# v0_4_0.net
KiCad netlist of a schematic drawn in EAGLE
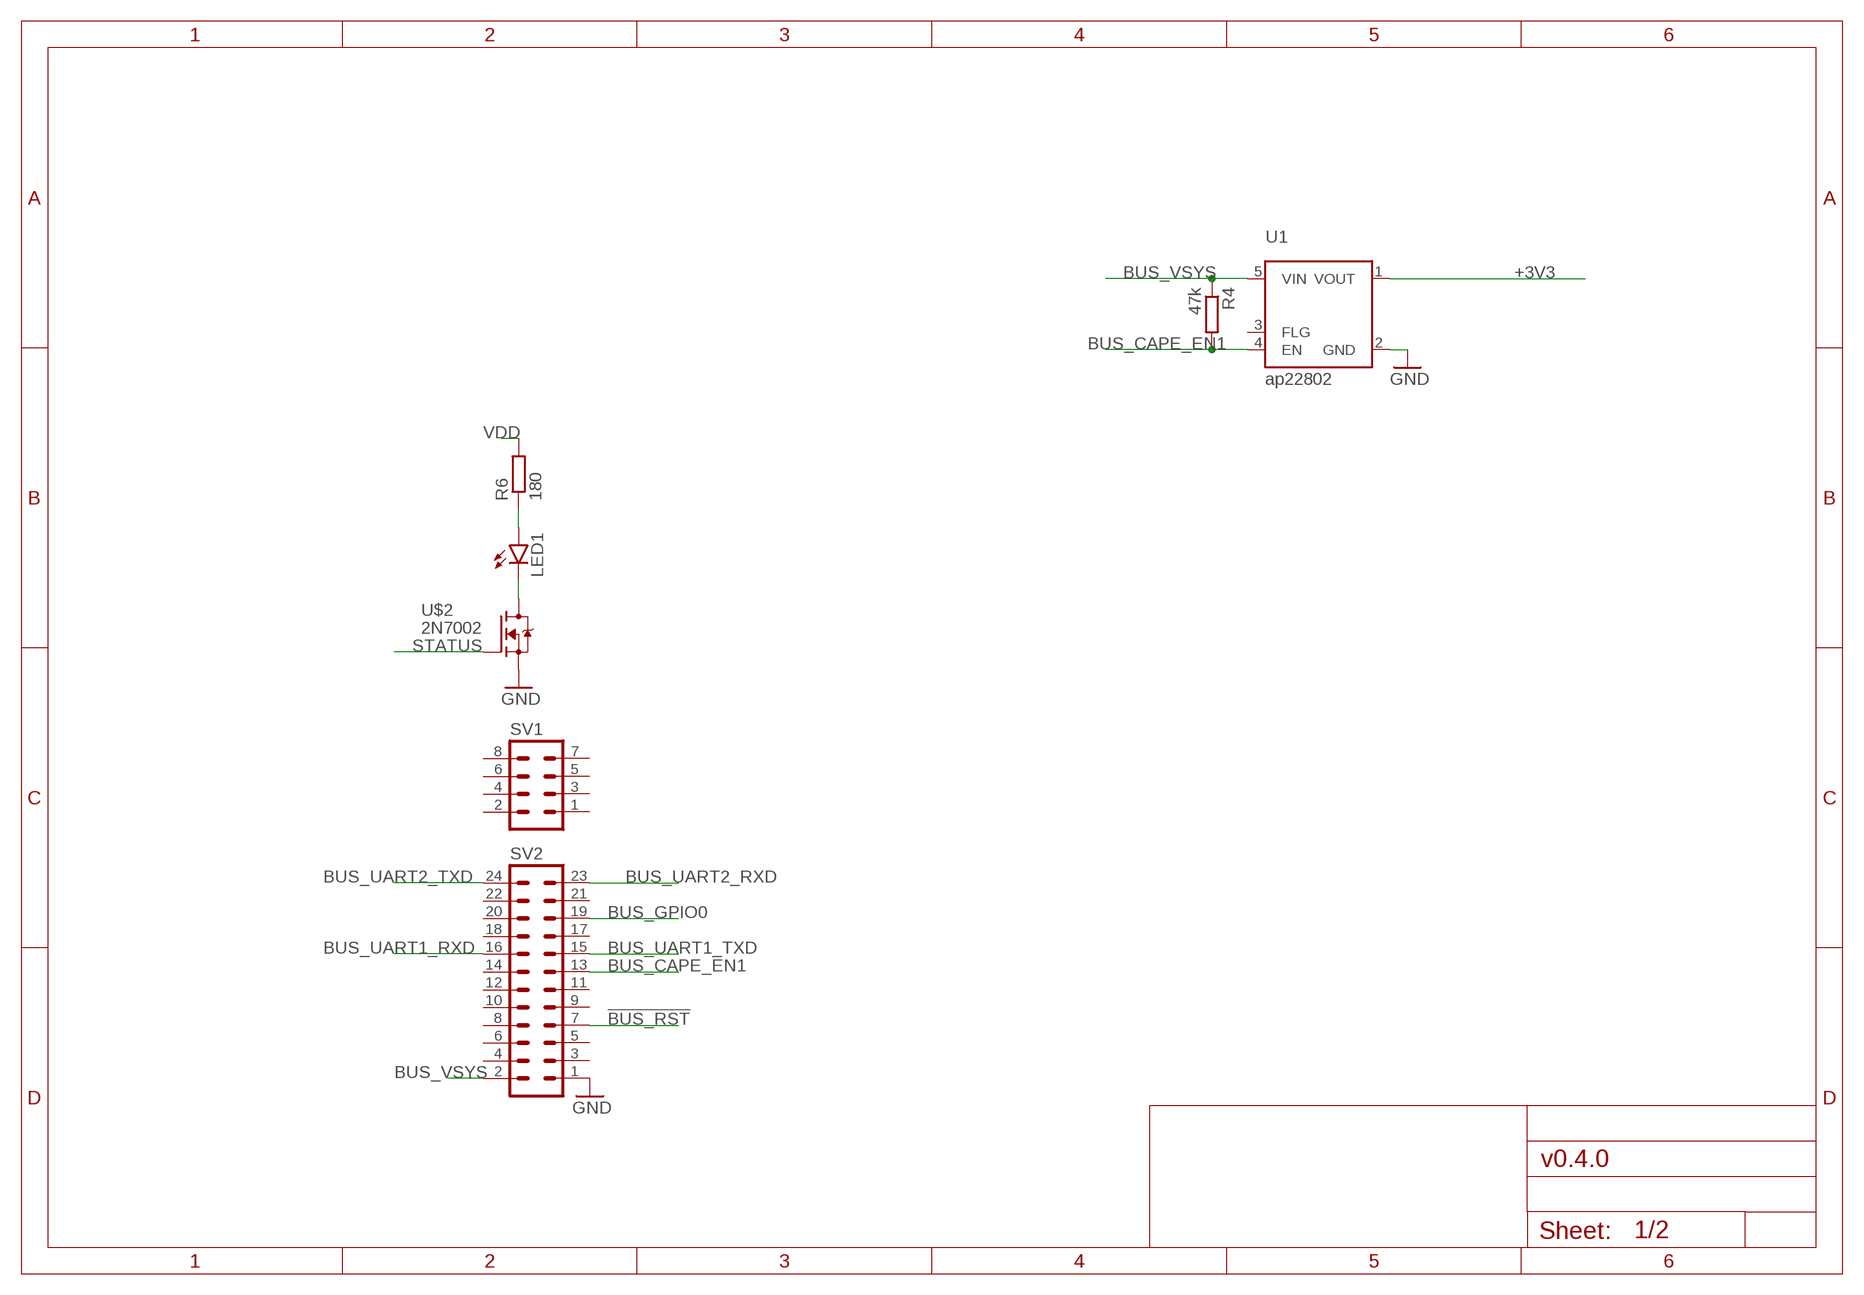
[diagram p0: schematic, sheet 1]
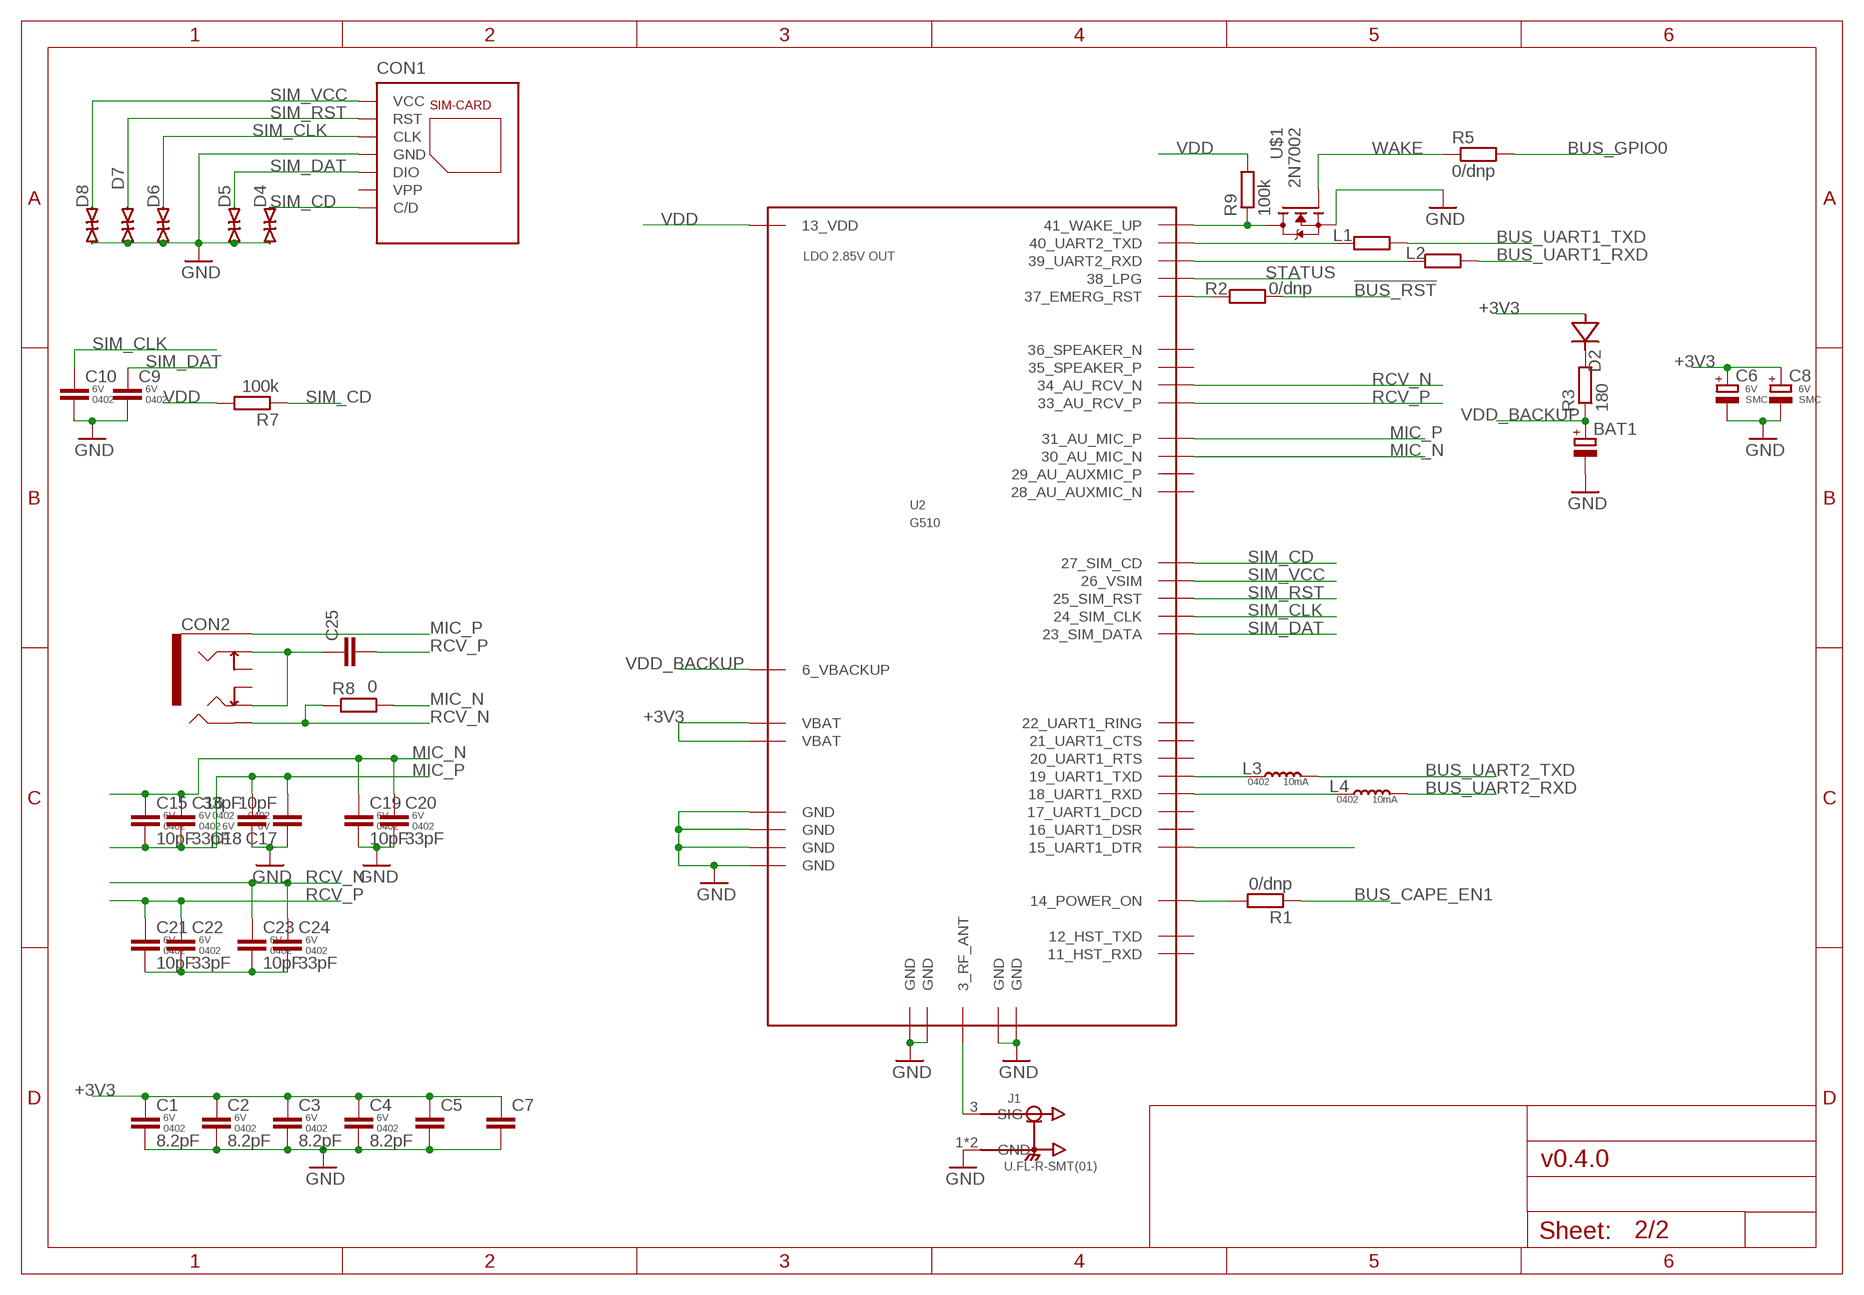
[diagram p1: schematic, sheet 2]

(export (version "E")
  (design (tool "Eeschema 10.0.6"))
  (components
    (comp (ref "BAT1")
      (value "DCK-3R3E224U-E")
      (footprint "eagle-import:621")
      (libsource (lib "eagle-import") (part "DCK-3R3E224U-E"))
    )
    (comp (ref "C1")
      (value "8.2pF")
      (footprint "eagle-import:C0402K")
      (libsource (lib "eagle-import") (part "CAP-0402"))
    )
    (comp (ref "C2")
      (value "8.2pF")
      (footprint "eagle-import:C0402K")
      (libsource (lib "eagle-import") (part "CAP-0402"))
    )
    (comp (ref "C3")
      (value "8.2pF")
      (footprint "eagle-import:C0402K")
      (libsource (lib "eagle-import") (part "CAP-0402"))
    )
    (comp (ref "C4")
      (value "8.2pF")
      (footprint "eagle-import:C0402K")
      (libsource (lib "eagle-import") (part "CAP-0402"))
    )
    (comp (ref "C5")
      (value "C-EUC0603")
      (footprint "eagle-import:C0603")
      (libsource (lib "eagle-import") (part "C-EUC0603"))
    )
    (comp (ref "C6")
      (value "CAP-POL-SMC")
      (footprint "eagle-import:SMC_C")
      (libsource (lib "eagle-import") (part "CAP-POL-SMC"))
    )
    (comp (ref "C7")
      (value "C-EUC0603")
      (footprint "eagle-import:C0603")
      (libsource (lib "eagle-import") (part "C-EUC0603"))
    )
    (comp (ref "C8")
      (value "CAP-POL-SMC")
      (footprint "eagle-import:SMC_C")
      (libsource (lib "eagle-import") (part "CAP-POL-SMC"))
    )
    (comp (ref "C9")
      (value "CAP-0402")
      (footprint "eagle-import:C0402K")
      (libsource (lib "eagle-import") (part "CAP-0402"))
    )
    (comp (ref "C10")
      (value "CAP-0402")
      (footprint "eagle-import:C0402K")
      (libsource (lib "eagle-import") (part "CAP-0402"))
    )
    (comp (ref "C15")
      (value "10pF")
      (footprint "eagle-import:C0402K")
      (libsource (lib "eagle-import") (part "CAP-0402"))
    )
    (comp (ref "C16")
      (value "33pF")
      (footprint "eagle-import:C0402K")
      (libsource (lib "eagle-import") (part "CAP-0402"))
    )
    (comp (ref "C17")
      (value "10pF")
      (footprint "eagle-import:C0402K")
      (libsource (lib "eagle-import") (part "CAP-0402"))
    )
    (comp (ref "C18")
      (value "33pF")
      (footprint "eagle-import:C0402K")
      (libsource (lib "eagle-import") (part "CAP-0402"))
    )
    (comp (ref "C19")
      (value "10pF")
      (footprint "eagle-import:C0402K")
      (libsource (lib "eagle-import") (part "CAP-0402"))
    )
    (comp (ref "C20")
      (value "33pF")
      (footprint "eagle-import:C0402K")
      (libsource (lib "eagle-import") (part "CAP-0402"))
    )
    (comp (ref "C21")
      (value "10pF")
      (footprint "eagle-import:C0402K")
      (libsource (lib "eagle-import") (part "CAP-0402"))
    )
    (comp (ref "C22")
      (value "33pF")
      (footprint "eagle-import:C0402K")
      (libsource (lib "eagle-import") (part "CAP-0402"))
    )
    (comp (ref "C23")
      (value "10pF")
      (footprint "eagle-import:C0402K")
      (libsource (lib "eagle-import") (part "CAP-0402"))
    )
    (comp (ref "C24")
      (value "33pF")
      (footprint "eagle-import:C0402K")
      (libsource (lib "eagle-import") (part "CAP-0402"))
    )
    (comp (ref "C25")
      (value "C-EUC0603")
      (footprint "eagle-import:C0603")
      (libsource (lib "eagle-import") (part "C-EUC0603"))
    )
    (comp (ref "CON1")
      (value "115Q-BCA0")
      (footprint "eagle-import:115Q")
      (libsource (lib "eagle-import") (part "115Q-BCA0"))
    )
    (comp (ref "CON2")
      (value "1503-21")
      (footprint "eagle-import:150321")
      (libsource (lib "eagle-import") (part "1503-21"))
    )
    (comp (ref "D2")
      (value "1N4148WS")
      (footprint "eagle-import:SOD323")
      (libsource (lib "eagle-import") (part "1N4148WS"))
    )
    (comp (ref "D4")
      (value "ESD9B5.0ST5G")
      (footprint "eagle-import:SOD1006X40")
      (libsource (lib "eagle-import") (part "ESD9B5.0ST5G"))
    )
    (comp (ref "D5")
      (value "ESD9B5.0ST5G")
      (footprint "eagle-import:SOD1006X40")
      (libsource (lib "eagle-import") (part "ESD9B5.0ST5G"))
    )
    (comp (ref "D6")
      (value "ESD9B5.0ST5G")
      (footprint "eagle-import:SOD1006X40")
      (libsource (lib "eagle-import") (part "ESD9B5.0ST5G"))
    )
    (comp (ref "D7")
      (value "ESD9B5.0ST5G")
      (footprint "eagle-import:SOD1006X40")
      (libsource (lib "eagle-import") (part "ESD9B5.0ST5G"))
    )
    (comp (ref "D8")
      (value "ESD9B5.0ST5G")
      (footprint "eagle-import:SOD1006X40")
      (libsource (lib "eagle-import") (part "ESD9B5.0ST5G"))
    )
    (comp (ref "J1")
      (value "U.FL-R-SMT(01)")
      (footprint "eagle-import:HRS_U.FL-R-SMT(01)")
      (fields (field (name "MF") "Hirose") (field (name "MP") "U.FL-R-SMT_01_"))
      (libsource (lib "eagle-import") (part "U.FL-R-SMT(01)"))
    )
    (comp (ref "L1")
      (value "R-EU_R0402")
      (footprint "eagle-import:R0402")
      (libsource (lib "eagle-import") (part "R-EU_R0402"))
    )
    (comp (ref "L2")
      (value "R-EU_R0402")
      (footprint "eagle-import:R0402")
      (libsource (lib "eagle-import") (part "R-EU_R0402"))
    )
    (comp (ref "L3")
      (value "IND-0402")
      (footprint "eagle-import:L0402")
      (libsource (lib "eagle-import") (part "IND-0402"))
    )
    (comp (ref "L4")
      (value "IND-0402")
      (footprint "eagle-import:L0402")
      (libsource (lib "eagle-import") (part "IND-0402"))
    )
    (comp (ref "R1")
      (value "0/dnp")
      (footprint "eagle-import:R0402")
      (libsource (lib "eagle-import") (part "R-EU_R0402"))
    )
    (comp (ref "R2")
      (value "0/dnp")
      (footprint "eagle-import:R0402")
      (libsource (lib "eagle-import") (part "R-EU_R0402"))
    )
    (comp (ref "R3")
      (value "180")
      (footprint "eagle-import:R0402")
      (libsource (lib "eagle-import") (part "R-EU_R0402"))
    )
    (comp (ref "R5")
      (value "0/dnp")
      (footprint "eagle-import:R0402")
      (libsource (lib "eagle-import") (part "R-EU_R0402"))
    )
    (comp (ref "R7")
      (value "100k")
      (footprint "eagle-import:R0402")
      (libsource (lib "eagle-import") (part "R-EU_R0402"))
    )
    (comp (ref "R8")
      (value "0")
      (footprint "eagle-import:R0402")
      (libsource (lib "eagle-import") (part "R-EU_R0402"))
    )
    (comp (ref "R9")
      (value "100k")
      (footprint "eagle-import:R0402")
      (libsource (lib "eagle-import") (part "R-EU_R0402"))
    )
    (comp (ref "U$1")
      (value "2N7002")
      (footprint "eagle-import:SOT95P240X110-3")
      (libsource (lib "eagle-import") (part "2N7002"))
    )
    (comp (ref "U2")
      (value "G510")
      (footprint "eagle-import:G510")
      (libsource (lib "eagle-import") (part "G510"))
    )
    (comp (ref "LED1")
      (value "LEDCHIP-LED0603")
      (footprint "eagle-import:CHIP-LED0603")
      (libsource (lib "eagle-import") (part "LEDCHIP-LED0603"))
    )
    (comp (ref "R4")
      (value "47k")
      (footprint "eagle-import:R0402")
      (libsource (lib "eagle-import") (part "R-EU_R0402"))
    )
    (comp (ref "R6")
      (value "180")
      (footprint "eagle-import:R0402")
      (libsource (lib "eagle-import") (part "R-EU_R0402"))
    )
    (comp (ref "SV1")
      (value "MA04-2")
      (footprint "eagle-import:MA04-2")
      (libsource (lib "eagle-import") (part "MA04-2"))
    )
    (comp (ref "SV2")
      (value "MA12-2")
      (footprint "eagle-import:MA12-2")
      (libsource (lib "eagle-import") (part "MA12-2"))
    )
    (comp (ref "U$2")
      (value "2N7002")
      (footprint "eagle-import:SOT95P240X110-3")
      (libsource (lib "eagle-import") (part "2N7002"))
    )
    (comp (ref "U1")
      (value "ap22802")
      (footprint "eagle-import:SOT25")
      (libsource (lib "eagle-import") (part "AP22802"))
    )
  )
  (nets
    (net (code "1") (name "+3V3") (class "Default")
      (node (ref "C1") (pin "1") (pinfunction "1_1") (pintype "passive"))
      (node (ref "C2") (pin "1") (pinfunction "1_1") (pintype "passive"))
      (node (ref "C3") (pin "1") (pinfunction "1_1") (pintype "passive"))
      (node (ref "C4") (pin "1") (pinfunction "1_1") (pintype "passive"))
      (node (ref "C5") (pin "1") (pinfunction "1_1") (pintype "passive"))
      (node (ref "C6") (pin "+") (pinfunction "+_+") (pintype "passive"))
      (node (ref "C7") (pin "1") (pinfunction "1_1") (pintype "passive"))
      (node (ref "C8") (pin "+") (pinfunction "+_+") (pintype "passive"))
      (node (ref "D2") (pin "A") (pinfunction "A_A") (pintype "passive"))
      (node (ref "U1") (pin "1") (pinfunction "VOUT_1") (pintype "bidirectional"))
      (node (ref "U2") (pin "10_VBAT") (pinfunction "VBAT_10_VBAT") (pintype "power_in"))
      (node (ref "U2") (pin "9_VBAT") (pinfunction "VBAT_9_VBAT") (pintype "power_in"))
    )
    (net (code "2") (name "BUS_CAPE_EN1") (class "Default")
      (node (ref "R1") (pin "1") (pinfunction "1_1") (pintype "passive"))
      (node (ref "R4") (pin "2") (pinfunction "2_2") (pintype "passive"))
      (node (ref "SV2") (pin "13") (pinfunction "13_13") (pintype "passive"))
      (node (ref "U1") (pin "4") (pinfunction "EN_4") (pintype "bidirectional"))
    )
    (net (code "3") (name "BUS_GPIO0") (class "Default")
      (node (ref "R5") (pin "2") (pinfunction "2_2") (pintype "passive"))
      (node (ref "SV2") (pin "19") (pinfunction "19_19") (pintype "passive"))
    )
    (net (code "4") (name "BUS_UART1_RXD") (class "Default")
      (node (ref "L2") (pin "2") (pinfunction "2_2") (pintype "passive"))
      (node (ref "SV2") (pin "16") (pinfunction "16_16") (pintype "passive"))
    )
    (net (code "5") (name "BUS_UART1_TXD") (class "Default")
      (node (ref "L1") (pin "2") (pinfunction "2_2") (pintype "passive"))
      (node (ref "SV2") (pin "15") (pinfunction "15_15") (pintype "passive"))
    )
    (net (code "6") (name "BUS_UART2_RXD") (class "Default")
      (node (ref "L4") (pin "2") (pinfunction "2_2") (pintype "passive"))
      (node (ref "SV2") (pin "23") (pinfunction "23_23") (pintype "passive"))
    )
    (net (code "7") (name "BUS_UART2_TXD") (class "Default")
      (node (ref "L3") (pin "2") (pinfunction "2_2") (pintype "passive"))
      (node (ref "SV2") (pin "24") (pinfunction "24_24") (pintype "passive"))
    )
    (net (code "8") (name "BUS_VSYS") (class "Default")
      (node (ref "R4") (pin "1") (pinfunction "1_1") (pintype "passive"))
      (node (ref "SV2") (pin "2") (pinfunction "2_2") (pintype "passive"))
      (node (ref "U1") (pin "5") (pinfunction "VIN_5") (pintype "bidirectional"))
    )
    (net (code "9") (name "GND") (class "Default")
      (node (ref "BAT1") (pin "-") (pinfunction "-_-") (pintype "passive"))
      (node (ref "C1") (pin "2") (pinfunction "2_2") (pintype "passive"))
      (node (ref "C10") (pin "2") (pinfunction "2_2") (pintype "passive"))
      (node (ref "C17") (pin "1") (pinfunction "1_1") (pintype "passive"))
      (node (ref "C18") (pin "1") (pinfunction "1_1") (pintype "passive"))
      (node (ref "C19") (pin "2") (pinfunction "2_2") (pintype "passive"))
      (node (ref "C2") (pin "2") (pinfunction "2_2") (pintype "passive"))
      (node (ref "C20") (pin "2") (pinfunction "2_2") (pintype "passive"))
      (node (ref "C3") (pin "2") (pinfunction "2_2") (pintype "passive"))
      (node (ref "C4") (pin "2") (pinfunction "2_2") (pintype "passive"))
      (node (ref "C5") (pin "2") (pinfunction "2_2") (pintype "passive"))
      (node (ref "C6") (pin "-") (pinfunction "-_-") (pintype "passive"))
      (node (ref "C7") (pin "2") (pinfunction "2_2") (pintype "passive"))
      (node (ref "C8") (pin "-") (pinfunction "-_-") (pintype "passive"))
      (node (ref "C9") (pin "2") (pinfunction "2_2") (pintype "passive"))
      (node (ref "CON1") (pin "GND1") (pinfunction "GND_GND1") (pintype "passive"))
      (node (ref "CON1") (pin "GND2") (pinfunction "GND_GND2") (pintype "passive"))
      (node (ref "CON1") (pin "GND3") (pinfunction "GND_GND3") (pintype "passive"))
      (node (ref "CON1") (pin "GND4") (pinfunction "GND_GND4") (pintype "passive"))
      (node (ref "CON1") (pin "P5") (pinfunction "GND_P5") (pintype "passive"))
      (node (ref "D4") (pin "1") (pinfunction "A_1") (pintype "passive"))
      (node (ref "D5") (pin "1") (pinfunction "A_1") (pintype "passive"))
      (node (ref "D6") (pin "1") (pinfunction "A_1") (pintype "passive"))
      (node (ref "D7") (pin "1") (pinfunction "A_1") (pintype "passive"))
      (node (ref "D8") (pin "1") (pinfunction "A_1") (pintype "passive"))
      (node (ref "J1") (pin "1") (pinfunction "GND_1") (pintype "passive"))
      (node (ref "J1") (pin "2") (pinfunction "GND_2") (pintype "passive"))
      (node (ref "SV2") (pin "1") (pinfunction "1_1") (pintype "passive"))
      (node (ref "U$1") (pin "2") (pinfunction "S_2") (pintype "passive"))
      (node (ref "U$2") (pin "2") (pinfunction "S_2") (pintype "passive"))
      (node (ref "U1") (pin "2") (pinfunction "GND_2") (pintype "bidirectional"))
      (node (ref "U2") (pin "1_GND") (pinfunction "GND_1_GND") (pintype "power_in"))
      (node (ref "U2") (pin "2_GND") (pinfunction "GND_2_GND") (pintype "power_in"))
      (node (ref "U2") (pin "32_GND") (pinfunction "GND_32_GND") (pintype "power_in"))
      (node (ref "U2") (pin "42_GND") (pinfunction "GND_42_GND") (pintype "power_in"))
      (node (ref "U2") (pin "4_GND") (pinfunction "GND_4_GND") (pintype "power_in"))
      (node (ref "U2") (pin "5_GND") (pinfunction "GND_5_GND") (pintype "power_in"))
      (node (ref "U2") (pin "7_GND") (pinfunction "GND_7_GND") (pintype "power_in"))
      (node (ref "U2") (pin "8_GND") (pinfunction "GND_8_GND") (pintype "power_in"))
    )
    (net (code "10") (name "MIC_N") (class "Default")
      (node (ref "C15") (pin "1") (pinfunction "1_1") (pintype "passive"))
      (node (ref "C16") (pin "1") (pinfunction "1_1") (pintype "passive"))
      (node (ref "C19") (pin "1") (pinfunction "1_1") (pintype "passive"))
      (node (ref "C20") (pin "1") (pinfunction "1_1") (pintype "passive"))
      (node (ref "R8") (pin "2") (pinfunction "2_2") (pintype "passive"))
      (node (ref "U2") (pin "30_AU_MIC_N") (pinfunction "30_AU_MIC_N_30_AU_MIC_N") (pintype "bidirectional"))
    )
    (net (code "11") (name "MIC_P") (class "Default")
      (node (ref "C15") (pin "2") (pinfunction "2_2") (pintype "passive"))
      (node (ref "C16") (pin "2") (pinfunction "2_2") (pintype "passive"))
      (node (ref "C17") (pin "2") (pinfunction "2_2") (pintype "passive"))
      (node (ref "C18") (pin "2") (pinfunction "2_2") (pintype "passive"))
      (node (ref "CON2") (pin "1") (pinfunction "1_1") (pintype "bidirectional"))
      (node (ref "U2") (pin "31_AU_MIC_P") (pinfunction "31_AU_MIC_P_31_AU_MIC_P") (pintype "bidirectional"))
    )
    (net (code "12") (name "Net-(C21-Pad2)") (class "Default")
      (node (ref "C21") (pin "2") (pinfunction "2_2") (pintype "passive"))
      (node (ref "C22") (pin "2") (pinfunction "2_2") (pintype "passive"))
      (node (ref "C23") (pin "2") (pinfunction "2_2") (pintype "passive"))
      (node (ref "C24") (pin "2") (pinfunction "2_2") (pintype "passive"))
    )
    (net (code "13") (name "Net-(C25-Pad1)") (class "Default")
      (node (ref "C25") (pin "1") (pinfunction "1_1") (pintype "passive"))
      (node (ref "CON2") (pin "3") (pinfunction "3_3") (pintype "bidirectional"))
      (node (ref "CON2") (pin "5") (pinfunction "5_5") (pintype "bidirectional"))
    )
    (net (code "14") (name "Net-(D2-C)") (class "Default")
      (node (ref "D2") (pin "K") (pinfunction "C_K") (pintype "passive"))
      (node (ref "R3") (pin "2") (pinfunction "2_2") (pintype "passive"))
    )
    (net (code "15") (name "Net-(J1-SIG)") (class "Default")
      (node (ref "J1") (pin "3") (pinfunction "SIG_3") (pintype "passive"))
      (node (ref "U2") (pin "3_RF_ANT") (pinfunction "3_RF_ANT_3_RF_ANT") (pintype "bidirectional"))
    )
    (net (code "16") (name "Net-(L1-Pad1)") (class "Default")
      (node (ref "L1") (pin "1") (pinfunction "1_1") (pintype "passive"))
      (node (ref "U2") (pin "40_UART2_TXD") (pinfunction "40_UART2_TXD_40_UART2_TXD") (pintype "output"))
    )
    (net (code "17") (name "Net-(L2-Pad1)") (class "Default")
      (node (ref "L2") (pin "1") (pinfunction "1_1") (pintype "passive"))
      (node (ref "U2") (pin "39_UART2_RXD") (pinfunction "39_UART2_RXD_39_UART2_RXD") (pintype "input"))
    )
    (net (code "18") (name "Net-(L3-Pad1)") (class "Default")
      (node (ref "L3") (pin "1") (pinfunction "1_1") (pintype "passive"))
      (node (ref "U2") (pin "19_UART1_TXD") (pinfunction "19_UART1_TXD_19_UART1_TXD") (pintype "output"))
    )
    (net (code "19") (name "Net-(L4-Pad1)") (class "Default")
      (node (ref "L4") (pin "1") (pinfunction "1_1") (pintype "passive"))
      (node (ref "U2") (pin "18_UART1_RXD") (pinfunction "18_UART1_RXD_18_UART1_RXD") (pintype "input"))
    )
    (net (code "20") (name "Net-(LED1-PadA)") (class "Default")
      (node (ref "LED1") (pin "A") (pinfunction "A_A") (pintype "passive"))
      (node (ref "R6") (pin "1") (pinfunction "1_1") (pintype "passive"))
    )
    (net (code "21") (name "Net-(R1-Pad2)") (class "Default")
      (node (ref "R1") (pin "2") (pinfunction "2_2") (pintype "passive"))
      (node (ref "U2") (pin "14_POWER_ON") (pinfunction "14_POWER_ON_14_POWER_ON") (pintype "input"))
    )
    (net (code "22") (name "Net-(R2-Pad1)") (class "Default")
      (node (ref "R2") (pin "1") (pinfunction "1_1") (pintype "passive"))
      (node (ref "U2") (pin "37_EMERG_RST") (pinfunction "37_EMERG_RST_37_EMERG_RST") (pintype "input"))
    )
    (net (code "23") (name "Net-(U$1-D)") (class "Default")
      (node (ref "R9") (pin "1") (pinfunction "1_1") (pintype "passive"))
      (node (ref "U$1") (pin "3") (pinfunction "D_3") (pintype "passive"))
      (node (ref "U2") (pin "41_WAKE_UP") (pinfunction "41_WAKE_UP_41_WAKE_UP") (pintype "bidirectional"))
    )
    (net (code "24") (name "Net-(U$2-D)") (class "Default")
      (node (ref "LED1") (pin "C") (pinfunction "C_C") (pintype "passive"))
      (node (ref "U$2") (pin "3") (pinfunction "D_3") (pintype "passive"))
    )
    (net (code "25") (name "RCV_N") (class "Default")
      (node (ref "C23") (pin "1") (pinfunction "1_1") (pintype "passive"))
      (node (ref "C24") (pin "1") (pinfunction "1_1") (pintype "passive"))
      (node (ref "CON2") (pin "2") (pinfunction "2_2") (pintype "bidirectional"))
      (node (ref "R8") (pin "1") (pinfunction "1_1") (pintype "passive"))
      (node (ref "U2") (pin "34_AU_RCV_N") (pinfunction "34_AU_RCV_N_34_AU_RCV_N") (pintype "bidirectional"))
    )
    (net (code "26") (name "RCV_P") (class "Default")
      (node (ref "C21") (pin "1") (pinfunction "1_1") (pintype "passive"))
      (node (ref "C22") (pin "1") (pinfunction "1_1") (pintype "passive"))
      (node (ref "C25") (pin "2") (pinfunction "2_2") (pintype "passive"))
      (node (ref "U2") (pin "33_AU_RCV_P") (pinfunction "33_AU_RCV_P_33_AU_RCV_P") (pintype "bidirectional"))
    )
    (net (code "27") (name "SIM_CD") (class "Default")
      (node (ref "CON1") (pin "CD") (pinfunction "C/D_CD") (pintype "passive"))
      (node (ref "D4") (pin "2") (pinfunction "C_2") (pintype "passive"))
      (node (ref "R7") (pin "1") (pinfunction "1_1") (pintype "passive"))
      (node (ref "U2") (pin "27_SIM_CD") (pinfunction "27_SIM_CD_27_SIM_CD") (pintype "bidirectional"))
    )
    (net (code "28") (name "SIM_CLK") (class "Default")
      (node (ref "C10") (pin "1") (pinfunction "1_1") (pintype "passive"))
      (node (ref "CON1") (pin "P3") (pinfunction "CLK_P3") (pintype "passive"))
      (node (ref "D6") (pin "2") (pinfunction "C_2") (pintype "passive"))
      (node (ref "U2") (pin "24_SIM_CLK") (pinfunction "24_SIM_CLK_24_SIM_CLK") (pintype "bidirectional"))
    )
    (net (code "29") (name "SIM_DAT") (class "Default")
      (node (ref "C9") (pin "1") (pinfunction "1_1") (pintype "passive"))
      (node (ref "CON1") (pin "P7") (pinfunction "DIO_P7") (pintype "passive"))
      (node (ref "D5") (pin "2") (pinfunction "C_2") (pintype "passive"))
      (node (ref "U2") (pin "23_SIM_DATA") (pinfunction "23_SIM_DATA_23_SIM_DATA") (pintype "bidirectional"))
    )
    (net (code "30") (name "SIM_RST") (class "Default")
      (node (ref "CON1") (pin "P2") (pinfunction "RST_P2") (pintype "passive"))
      (node (ref "D7") (pin "2") (pinfunction "C_2") (pintype "passive"))
      (node (ref "U2") (pin "25_SIM_RST") (pinfunction "25_SIM_RST_25_SIM_RST") (pintype "bidirectional"))
    )
    (net (code "31") (name "SIM_VCC") (class "Default")
      (node (ref "CON1") (pin "P1") (pinfunction "VCC_P1") (pintype "passive"))
      (node (ref "D8") (pin "2") (pinfunction "C_2") (pintype "passive"))
      (node (ref "U2") (pin "26_VSIM") (pinfunction "26_VSIM_26_VSIM") (pintype "bidirectional"))
    )
    (net (code "32") (name "STATUS") (class "Default")
      (node (ref "U$2") (pin "1") (pinfunction "G_1") (pintype "passive"))
      (node (ref "U2") (pin "38_LPG") (pinfunction "38_LPG_38_LPG") (pintype "output"))
    )
    (net (code "33") (name "VDD") (class "Default")
      (node (ref "R6") (pin "2") (pinfunction "2_2") (pintype "passive"))
      (node (ref "R7") (pin "2") (pinfunction "2_2") (pintype "passive"))
      (node (ref "R9") (pin "2") (pinfunction "2_2") (pintype "passive"))
      (node (ref "U2") (pin "13_VDD") (pinfunction "13_VDD_13_VDD") (pintype "power_in"))
    )
    (net (code "34") (name "VDD_BACKUP") (class "Default")
      (node (ref "BAT1") (pin "+") (pinfunction "+_+") (pintype "passive"))
      (node (ref "R3") (pin "1") (pinfunction "1_1") (pintype "passive"))
      (node (ref "U2") (pin "6_VBACKUP") (pinfunction "6_VBACKUP_6_VBACKUP") (pintype "power_in"))
    )
    (net (code "35") (name "WAKE") (class "Default")
      (node (ref "R5") (pin "1") (pinfunction "1_1") (pintype "passive"))
      (node (ref "U$1") (pin "1") (pinfunction "G_1") (pintype "passive"))
    )
    (net (code "36") (name "unconnected-(CON1-VPP-PadP6)") (class "Default")
      (node (ref "CON1") (pin "P6") (pinfunction "VPP_P6") (pintype "passive"))
    )
    (net (code "37") (name "unconnected-(CON2-Pad4)") (class "Default")
      (node (ref "CON2") (pin "4") (pinfunction "4_4") (pintype "bidirectional"))
    )
    (net (code "38") (name "unconnected-(CON2-Pad6)") (class "Default")
      (node (ref "CON2") (pin "6") (pinfunction "6_6") (pintype "bidirectional"))
    )
    (net (code "39") (name "unconnected-(SV1-Pad1)") (class "Default")
      (node (ref "SV1") (pin "1") (pinfunction "1_1") (pintype "passive"))
    )
    (net (code "40") (name "unconnected-(SV1-Pad2)") (class "Default")
      (node (ref "SV1") (pin "2") (pinfunction "2_2") (pintype "passive"))
    )
    (net (code "41") (name "unconnected-(SV1-Pad3)") (class "Default")
      (node (ref "SV1") (pin "3") (pinfunction "3_3") (pintype "passive"))
    )
    (net (code "42") (name "unconnected-(SV1-Pad4)") (class "Default")
      (node (ref "SV1") (pin "4") (pinfunction "4_4") (pintype "passive"))
    )
    (net (code "43") (name "unconnected-(SV1-Pad5)") (class "Default")
      (node (ref "SV1") (pin "5") (pinfunction "5_5") (pintype "passive"))
    )
    (net (code "44") (name "unconnected-(SV1-Pad6)") (class "Default")
      (node (ref "SV1") (pin "6") (pinfunction "6_6") (pintype "passive"))
    )
    (net (code "45") (name "unconnected-(SV1-Pad7)") (class "Default")
      (node (ref "SV1") (pin "7") (pinfunction "7_7") (pintype "passive"))
    )
    (net (code "46") (name "unconnected-(SV1-Pad8)") (class "Default")
      (node (ref "SV1") (pin "8") (pinfunction "8_8") (pintype "passive"))
    )
    (net (code "47") (name "unconnected-(SV2-Pad3)") (class "Default")
      (node (ref "SV2") (pin "3") (pinfunction "3_3") (pintype "passive"))
    )
    (net (code "48") (name "unconnected-(SV2-Pad4)") (class "Default")
      (node (ref "SV2") (pin "4") (pinfunction "4_4") (pintype "passive"))
    )
    (net (code "49") (name "unconnected-(SV2-Pad5)") (class "Default")
      (node (ref "SV2") (pin "5") (pinfunction "5_5") (pintype "passive"))
    )
    (net (code "50") (name "unconnected-(SV2-Pad6)") (class "Default")
      (node (ref "SV2") (pin "6") (pinfunction "6_6") (pintype "passive"))
    )
    (net (code "51") (name "unconnected-(SV2-Pad8)") (class "Default")
      (node (ref "SV2") (pin "8") (pinfunction "8_8") (pintype "passive"))
    )
    (net (code "52") (name "unconnected-(SV2-Pad9)") (class "Default")
      (node (ref "SV2") (pin "9") (pinfunction "9_9") (pintype "passive"))
    )
    (net (code "53") (name "unconnected-(SV2-Pad10)") (class "Default")
      (node (ref "SV2") (pin "10") (pinfunction "10_10") (pintype "passive"))
    )
    (net (code "54") (name "unconnected-(SV2-Pad11)") (class "Default")
      (node (ref "SV2") (pin "11") (pinfunction "11_11") (pintype "passive"))
    )
    (net (code "55") (name "unconnected-(SV2-Pad12)") (class "Default")
      (node (ref "SV2") (pin "12") (pinfunction "12_12") (pintype "passive"))
    )
    (net (code "56") (name "unconnected-(SV2-Pad14)") (class "Default")
      (node (ref "SV2") (pin "14") (pinfunction "14_14") (pintype "passive"))
    )
    (net (code "57") (name "unconnected-(SV2-Pad17)") (class "Default")
      (node (ref "SV2") (pin "17") (pinfunction "17_17") (pintype "passive"))
    )
    (net (code "58") (name "unconnected-(SV2-Pad18)") (class "Default")
      (node (ref "SV2") (pin "18") (pinfunction "18_18") (pintype "passive"))
    )
    (net (code "59") (name "unconnected-(SV2-Pad20)") (class "Default")
      (node (ref "SV2") (pin "20") (pinfunction "20_20") (pintype "passive"))
    )
    (net (code "60") (name "unconnected-(SV2-Pad21)") (class "Default")
      (node (ref "SV2") (pin "21") (pinfunction "21_21") (pintype "passive"))
    )
    (net (code "61") (name "unconnected-(SV2-Pad22)") (class "Default")
      (node (ref "SV2") (pin "22") (pinfunction "22_22") (pintype "passive"))
    )
    (net (code "62") (name "unconnected-(U1-FLG-Pad3)") (class "Default")
      (node (ref "U1") (pin "3") (pinfunction "FLG_3") (pintype "bidirectional"))
    )
    (net (code "63") (name "unconnected-(U2-11_HST_RXD-Pad11_HSTRXD)") (class "Default")
      (node (ref "U2") (pin "11_HSTRXD") (pinfunction "11_HST_RXD_11_HSTRXD") (pintype "input"))
    )
    (net (code "64") (name "unconnected-(U2-Pad12_HST_TXD)") (class "Default")
      (node (ref "U2") (pin "12_HST_TXD") (pinfunction "12_HST_TXD_12_HST_TXD") (pintype "output"))
    )
    (net (code "65") (name "unconnected-(U2-Pad15_UART1_DTR)") (class "Default")
      (node (ref "U2") (pin "15_UART1_DTR") (pinfunction "15_UART1_DTR_15_UART1_DTR") (pintype "bidirectional"))
    )
    (net (code "66") (name "unconnected-(U2-Pad16_UART1_DSR)") (class "Default")
      (node (ref "U2") (pin "16_UART1_DSR") (pinfunction "16_UART1_DSR_16_UART1_DSR") (pintype "bidirectional"))
    )
    (net (code "67") (name "unconnected-(U2-Pad17_UART1_DCD)") (class "Default")
      (node (ref "U2") (pin "17_UART1_DCD") (pinfunction "17_UART1_DCD_17_UART1_DCD") (pintype "bidirectional"))
    )
    (net (code "68") (name "unconnected-(U2-Pad20_UART1_RTS)") (class "Default")
      (node (ref "U2") (pin "20_UART1_RTS") (pinfunction "20_UART1_RTS_20_UART1_RTS") (pintype "bidirectional"))
    )
    (net (code "69") (name "unconnected-(U2-Pad21_UART1_CTS)") (class "Default")
      (node (ref "U2") (pin "21_UART1_CTS") (pinfunction "21_UART1_CTS_21_UART1_CTS") (pintype "bidirectional"))
    )
    (net (code "70") (name "unconnected-(U2-Pad22_UART1_RING)") (class "Default")
      (node (ref "U2") (pin "22_UART1_RING") (pinfunction "22_UART1_RING_22_UART1_RING") (pintype "bidirectional"))
    )
    (net (code "71") (name "unconnected-(U2-Pad28_AU_AUXMIC_N)") (class "Default")
      (node (ref "U2") (pin "28_AU_AUXMIC_N") (pinfunction "28_AU_AUXMIC_N_28_AU_AUXMIC_N") (pintype "bidirectional"))
    )
    (net (code "72") (name "unconnected-(U2-Pad29_AU_AUXMIC_P)") (class "Default")
      (node (ref "U2") (pin "29_AU_AUXMIC_P") (pinfunction "29_AU_AUXMIC_P_29_AU_AUXMIC_P") (pintype "bidirectional"))
    )
    (net (code "73") (name "unconnected-(U2-Pad35_SPEAKER_P)") (class "Default")
      (node (ref "U2") (pin "35_SPEAKER_P") (pinfunction "35_SPEAKER_P_35_SPEAKER_P") (pintype "bidirectional"))
    )
    (net (code "74") (name "unconnected-(U2-Pad36_SPEAKER_N)") (class "Default")
      (node (ref "U2") (pin "36_SPEAKER_N") (pinfunction "36_SPEAKER_N_36_SPEAKER_N") (pintype "bidirectional"))
    )
    (net (code "75") (name "~{BUS_RST}") (class "Default")
      (node (ref "R2") (pin "2") (pinfunction "2_2") (pintype "passive"))
      (node (ref "SV2") (pin "7") (pinfunction "7_7") (pintype "passive"))
    )
  )
)
